# led.net
KiCad netlist of a schematic drawn in Altium Designer
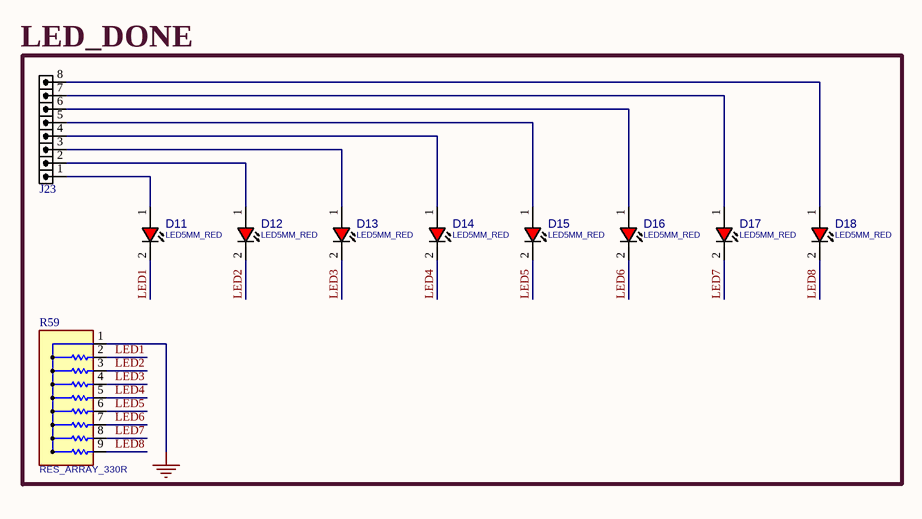
[diagram p0: led.SchDoc]

(export (version "E")
  (design (tool "Eeschema 10.0.6"))
  (components
    (comp (ref "D11")
      (value "LED5MM_RED")
      (footprint "LED5MM_RED")
      (description "LED, THD, 5MM, RED")
      (fields (field (name "MANF") "MANF") (field (name "MANF_P#") "MANF_PART#"))
      (libsource (lib "led(diode)") (part "LED_THD_5MM_RED"))
    )
    (comp (ref "D12")
      (value "LED5MM_RED")
      (footprint "LED5MM_RED")
      (description "LED, THD, 5MM, RED")
      (fields (field (name "MANF") "MANF") (field (name "MANF_P#") "MANF_PART#"))
      (libsource (lib "led(diode)") (part "LED_THD_5MM_RED"))
    )
    (comp (ref "D13")
      (value "LED5MM_RED")
      (footprint "LED5MM_RED")
      (description "LED, THD, 5MM, RED")
      (fields (field (name "MANF") "MANF") (field (name "MANF_P#") "MANF_PART#"))
      (libsource (lib "led(diode)") (part "LED_THD_5MM_RED"))
    )
    (comp (ref "D14")
      (value "LED5MM_RED")
      (footprint "LED5MM_RED")
      (description "LED, THD, 5MM, RED")
      (fields (field (name "MANF") "MANF") (field (name "MANF_P#") "MANF_PART#"))
      (libsource (lib "led(diode)") (part "LED_THD_5MM_RED"))
    )
    (comp (ref "D15")
      (value "LED5MM_RED")
      (footprint "LED5MM_RED")
      (description "LED, THD, 5MM, RED")
      (fields (field (name "MANF") "MANF") (field (name "MANF_P#") "MANF_PART#"))
      (libsource (lib "led(diode)") (part "LED_THD_5MM_RED"))
    )
    (comp (ref "D16")
      (value "LED5MM_RED")
      (footprint "LED5MM_RED")
      (description "LED, THD, 5MM, RED")
      (fields (field (name "MANF") "MANF") (field (name "MANF_P#") "MANF_PART#"))
      (libsource (lib "led(diode)") (part "LED_THD_5MM_RED"))
    )
    (comp (ref "D17")
      (value "LED5MM_RED")
      (footprint "LED5MM_RED")
      (description "LED, THD, 5MM, RED")
      (fields (field (name "MANF") "MANF") (field (name "MANF_P#") "MANF_PART#"))
      (libsource (lib "led(diode)") (part "LED_THD_5MM_RED"))
    )
    (comp (ref "D18")
      (value "LED5MM_RED")
      (footprint "LED5MM_RED")
      (description "LED, THD, 5MM, RED")
      (fields (field (name "MANF") "MANF") (field (name "MANF_P#") "MANF_PART#"))
      (libsource (lib "led(diode)") (part "LED_THD_5MM_RED"))
    )
    (comp (ref "J23")
      (value "HDR1X8")
      (footprint "HDR_M_1X8")
      (description "CONN, HEADER, Male, pitch: 2.54mm, 8POS")
      (libsource (lib "conn_header_2.54mm_st") (part "HDR_M_1X8"))
    )
    (comp (ref "R59")
      (value "RES_ARRAY_330R")
      (footprint "RES_ARRAYX8")
      (description "RESISTOR, THD, Array, 8RES")
      (libsource (lib "passive_thd") (part "RES_THD_ARRAY"))
    )
  )
  (nets
    (net (code "1") (name "/LED1") (class "Default")
      (node (ref "D11") (pin "2") (pinfunction "CATHODE_2") (pintype "passive"))
      (node (ref "R59") (pin "2") (pinfunction "2_2") (pintype "passive"))
    )
    (net (code "2") (name "/LED2") (class "Default")
      (node (ref "D12") (pin "2") (pinfunction "CATHODE_2") (pintype "passive"))
      (node (ref "R59") (pin "3") (pinfunction "3_3") (pintype "passive"))
    )
    (net (code "3") (name "/LED3") (class "Default")
      (node (ref "D13") (pin "2") (pinfunction "CATHODE_2") (pintype "passive"))
      (node (ref "R59") (pin "4") (pinfunction "4_4") (pintype "passive"))
    )
    (net (code "4") (name "/LED4") (class "Default")
      (node (ref "D14") (pin "2") (pinfunction "CATHODE_2") (pintype "passive"))
      (node (ref "R59") (pin "5") (pinfunction "5_5") (pintype "passive"))
    )
    (net (code "5") (name "/LED5") (class "Default")
      (node (ref "D15") (pin "2") (pinfunction "CATHODE_2") (pintype "passive"))
      (node (ref "R59") (pin "6") (pinfunction "6_6") (pintype "passive"))
    )
    (net (code "6") (name "/LED6") (class "Default")
      (node (ref "D16") (pin "2") (pinfunction "CATHODE_2") (pintype "passive"))
      (node (ref "R59") (pin "7") (pinfunction "7_7") (pintype "passive"))
    )
    (net (code "7") (name "/LED7") (class "Default")
      (node (ref "D17") (pin "2") (pinfunction "CATHODE_2") (pintype "passive"))
      (node (ref "R59") (pin "8") (pinfunction "8_8") (pintype "passive"))
    )
    (net (code "8") (name "/LED8") (class "Default")
      (node (ref "D18") (pin "2") (pinfunction "CATHODE_2") (pintype "passive"))
      (node (ref "R59") (pin "9") (pinfunction "9_9") (pintype "passive"))
    )
    (net (code "9") (name "GND") (class "Default")
      (node (ref "R59") (pin "1") (pinfunction "1_1") (pintype "passive"))
    )
    (net (code "10") (name "Net-(D11-ANODE)") (class "Default")
      (node (ref "D11") (pin "1") (pinfunction "ANODE_1") (pintype "passive"))
      (node (ref "J23") (pin "1") (pinfunction "1_1") (pintype "passive"))
    )
    (net (code "11") (name "Net-(D12-ANODE)") (class "Default")
      (node (ref "D12") (pin "1") (pinfunction "ANODE_1") (pintype "passive"))
      (node (ref "J23") (pin "2") (pinfunction "2_2") (pintype "passive"))
    )
    (net (code "12") (name "Net-(D13-ANODE)") (class "Default")
      (node (ref "D13") (pin "1") (pinfunction "ANODE_1") (pintype "passive"))
      (node (ref "J23") (pin "3") (pinfunction "3_3") (pintype "passive"))
    )
    (net (code "13") (name "Net-(D14-ANODE)") (class "Default")
      (node (ref "D14") (pin "1") (pinfunction "ANODE_1") (pintype "passive"))
      (node (ref "J23") (pin "4") (pinfunction "4_4") (pintype "passive"))
    )
    (net (code "14") (name "Net-(D15-ANODE)") (class "Default")
      (node (ref "D15") (pin "1") (pinfunction "ANODE_1") (pintype "passive"))
      (node (ref "J23") (pin "5") (pinfunction "5_5") (pintype "passive"))
    )
    (net (code "15") (name "Net-(D16-ANODE)") (class "Default")
      (node (ref "D16") (pin "1") (pinfunction "ANODE_1") (pintype "passive"))
      (node (ref "J23") (pin "6") (pinfunction "6_6") (pintype "passive"))
    )
    (net (code "16") (name "Net-(D17-ANODE)") (class "Default")
      (node (ref "D17") (pin "1") (pinfunction "ANODE_1") (pintype "passive"))
      (node (ref "J23") (pin "7") (pinfunction "7_7") (pintype "passive"))
    )
    (net (code "17") (name "Net-(D18-ANODE)") (class "Default")
      (node (ref "D18") (pin "1") (pinfunction "ANODE_1") (pintype "passive"))
      (node (ref "J23") (pin "8") (pinfunction "8_8") (pintype "passive"))
    )
  )
)
